# sdr_3157.net
KiCad netlist of a schematic drawn in EAGLE
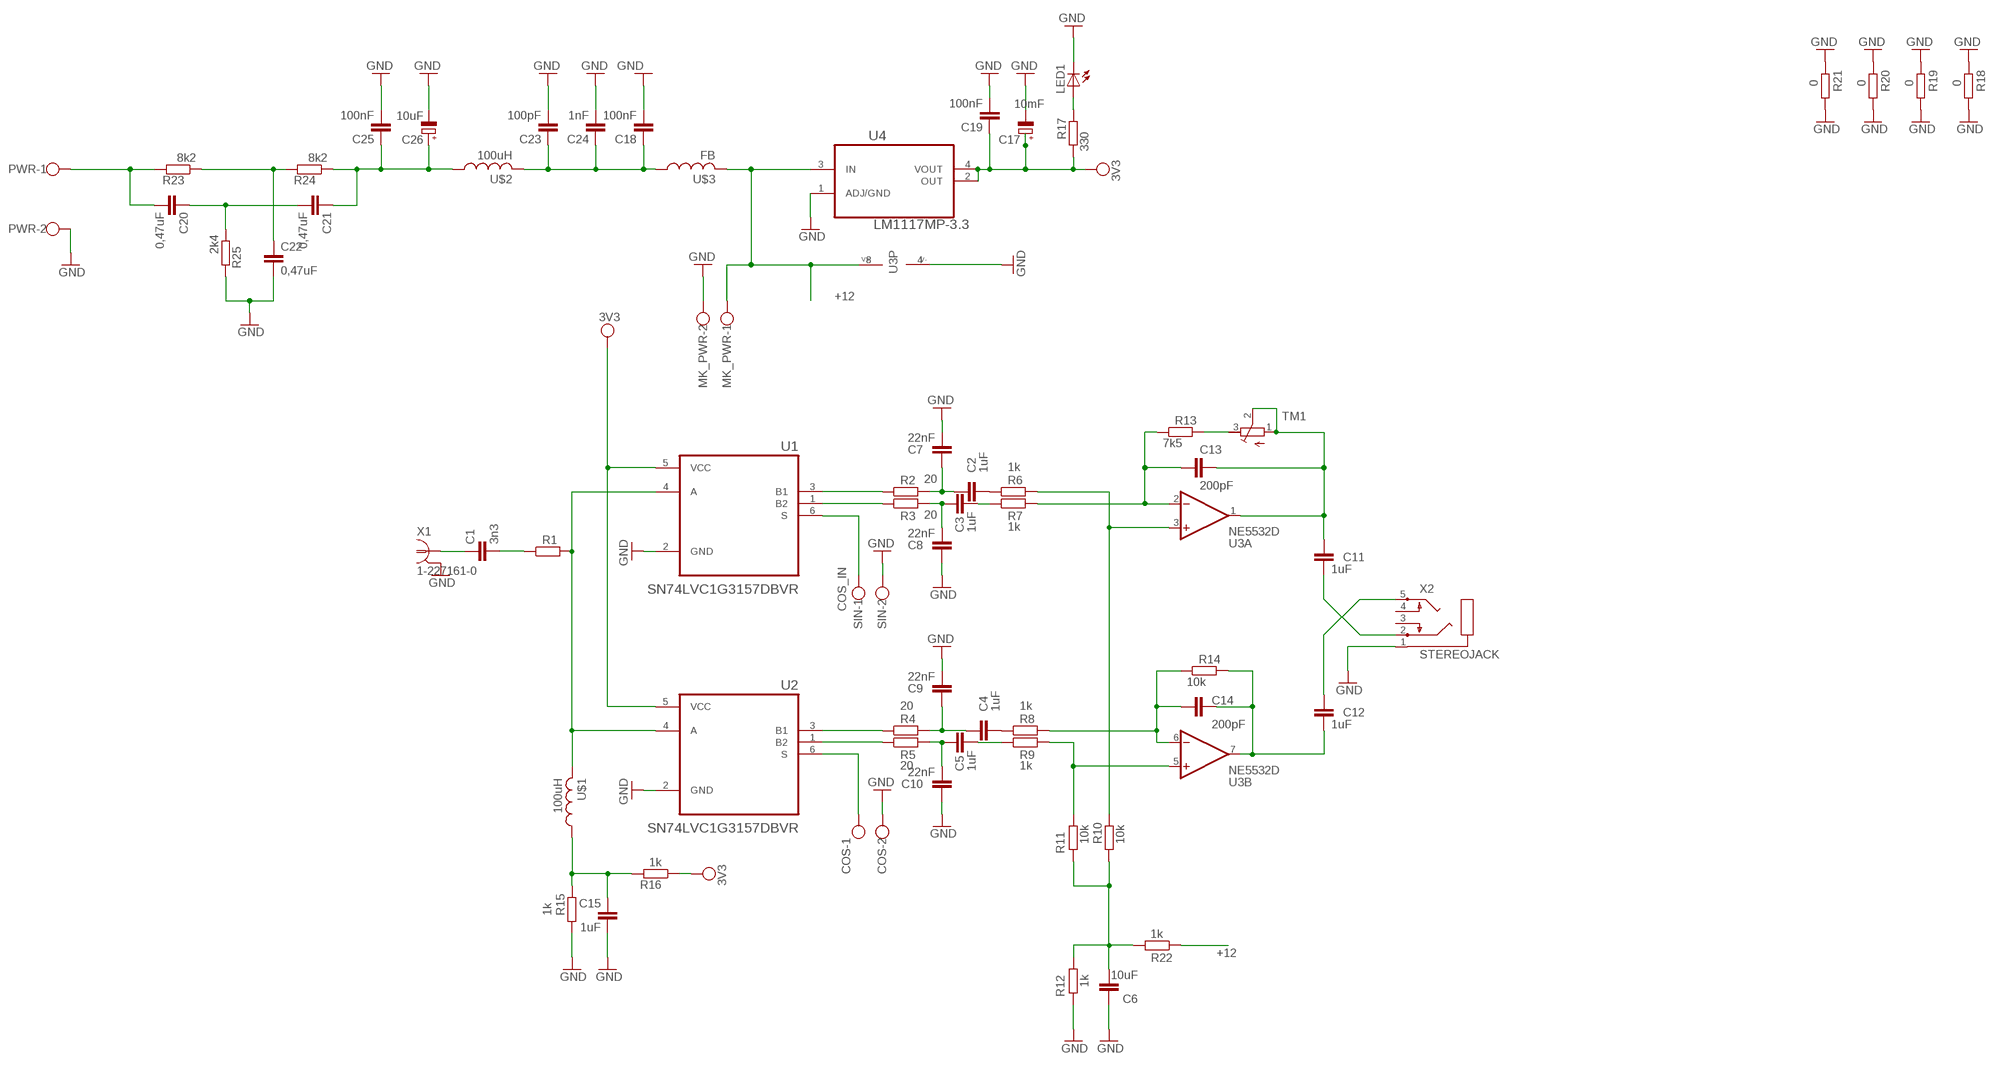
[diagram p0: schematic, sheet 1]

(export (version "E")
  (design (tool "Eeschema 10.0.6"))
  (components
    (comp (ref "C1")
      (value "3n3")
      (footprint "eagle-import:C0805")
      (libsource (lib "eagle-import") (part "C-EUC0805"))
    )
    (comp (ref "C2")
      (value "1uF")
      (footprint "eagle-import:C0805")
      (libsource (lib "eagle-import") (part "C-EUC0805"))
    )
    (comp (ref "C3")
      (value "1uF")
      (footprint "eagle-import:C0805")
      (libsource (lib "eagle-import") (part "C-EUC0805"))
    )
    (comp (ref "C4")
      (value "1uF")
      (footprint "eagle-import:C0805")
      (libsource (lib "eagle-import") (part "C-EUC0805"))
    )
    (comp (ref "C5")
      (value "1uF")
      (footprint "eagle-import:C0805")
      (libsource (lib "eagle-import") (part "C-EUC0805"))
    )
    (comp (ref "C6")
      (value "10uF")
      (footprint "eagle-import:C0805")
      (libsource (lib "eagle-import") (part "C-EUC0805"))
    )
    (comp (ref "C7")
      (value "22nF")
      (footprint "eagle-import:C0805")
      (libsource (lib "eagle-import") (part "C-EUC0805"))
    )
    (comp (ref "C8")
      (value "22nF")
      (footprint "eagle-import:C0805")
      (libsource (lib "eagle-import") (part "C-EUC0805"))
    )
    (comp (ref "C9")
      (value "22nF")
      (footprint "eagle-import:C0805")
      (libsource (lib "eagle-import") (part "C-EUC0805"))
    )
    (comp (ref "C10")
      (value "22nF")
      (footprint "eagle-import:C0805")
      (libsource (lib "eagle-import") (part "C-EUC0805"))
    )
    (comp (ref "C11")
      (value "1uF")
      (footprint "eagle-import:C1210K")
      (libsource (lib "eagle-import") (part "C-EUC1210K"))
    )
    (comp (ref "C12")
      (value "1uF")
      (footprint "eagle-import:C1210K")
      (libsource (lib "eagle-import") (part "C-EUC1210K"))
    )
    (comp (ref "C13")
      (value "200pF")
      (footprint "eagle-import:C0805")
      (libsource (lib "eagle-import") (part "C-EUC0805"))
    )
    (comp (ref "C14")
      (value "200pF")
      (footprint "eagle-import:C0805")
      (libsource (lib "eagle-import") (part "C-EUC0805"))
    )
    (comp (ref "C15")
      (value "1uF")
      (footprint "eagle-import:C0805")
      (libsource (lib "eagle-import") (part "C-EUC0805"))
    )
    (comp (ref "C17")
      (value "10mF")
      (footprint "eagle-import:SMC_C")
      (libsource (lib "eagle-import") (part "CPOL-EUSMCC"))
    )
    (comp (ref "C18")
      (value "100nF")
      (footprint "eagle-import:C0805")
      (libsource (lib "eagle-import") (part "C-EUC0805"))
    )
    (comp (ref "C19")
      (value "100nF")
      (footprint "eagle-import:C0805")
      (libsource (lib "eagle-import") (part "C-EUC0805"))
    )
    (comp (ref "C20")
      (value "0,47uF")
      (footprint "eagle-import:C0805")
      (libsource (lib "eagle-import") (part "C-EUC0805"))
    )
    (comp (ref "C21")
      (value "0,47uF")
      (footprint "eagle-import:C0805")
      (libsource (lib "eagle-import") (part "C-EUC0805"))
    )
    (comp (ref "C22")
      (value "0,47uF")
      (footprint "eagle-import:C0805")
      (libsource (lib "eagle-import") (part "C-EUC0805"))
    )
    (comp (ref "C23")
      (value "100pF")
      (footprint "eagle-import:C0805")
      (libsource (lib "eagle-import") (part "C-EUC0805"))
    )
    (comp (ref "C24")
      (value "1nF")
      (footprint "eagle-import:C0805")
      (libsource (lib "eagle-import") (part "C-EUC0805"))
    )
    (comp (ref "C25")
      (value "100nF")
      (footprint "eagle-import:C0805")
      (libsource (lib "eagle-import") (part "C-EUC0805"))
    )
    (comp (ref "C26")
      (value "10uF")
      (footprint "eagle-import:SMC_C")
      (libsource (lib "eagle-import") (part "CPOL-EUSMCC"))
    )
    (comp (ref "COS")
      (value "W237-102")
      (footprint "eagle-import:W237-102")
      (fields (field (name "MPN") "237-102"))
      (libsource (lib "eagle-import") (part "W237-102"))
    )
    (comp (ref "LED1")
      (value "LEDSMT1206")
      (footprint "eagle-import:1206")
      (libsource (lib "eagle-import") (part "LEDSMT1206"))
    )
    (comp (ref "MK_PWR")
      (value "W237-102")
      (footprint "eagle-import:W237-102")
      (fields (field (name "MPN") "237-102"))
      (libsource (lib "eagle-import") (part "W237-102"))
    )
    (comp (ref "PWR")
      (value "W237-102")
      (footprint "eagle-import:W237-102")
      (fields (field (name "MPN") "237-102"))
      (libsource (lib "eagle-import") (part "W237-102"))
    )
    (comp (ref "R1")
      (value "R-EU_R0805")
      (footprint "eagle-import:R0805")
      (libsource (lib "eagle-import") (part "R-EU_R0805"))
    )
    (comp (ref "R2")
      (value "20")
      (footprint "eagle-import:R0805")
      (libsource (lib "eagle-import") (part "R-EU_R0805"))
    )
    (comp (ref "R3")
      (value "20")
      (footprint "eagle-import:R0805")
      (libsource (lib "eagle-import") (part "R-EU_R0805"))
    )
    (comp (ref "R4")
      (value "20")
      (footprint "eagle-import:R0805")
      (libsource (lib "eagle-import") (part "R-EU_R0805"))
    )
    (comp (ref "R5")
      (value "20")
      (footprint "eagle-import:R0805")
      (libsource (lib "eagle-import") (part "R-EU_R0805"))
    )
    (comp (ref "R6")
      (value "1k")
      (footprint "eagle-import:R0805")
      (libsource (lib "eagle-import") (part "R-EU_R0805"))
    )
    (comp (ref "R7")
      (value "1k")
      (footprint "eagle-import:R0805")
      (libsource (lib "eagle-import") (part "R-EU_R0805"))
    )
    (comp (ref "R8")
      (value "1k")
      (footprint "eagle-import:0204_7")
      (libsource (lib "eagle-import") (part "R-EU_0204/7"))
    )
    (comp (ref "R9")
      (value "1k")
      (footprint "eagle-import:R0805")
      (libsource (lib "eagle-import") (part "R-EU_R0805"))
    )
    (comp (ref "R10")
      (value "10k")
      (footprint "eagle-import:R0805")
      (libsource (lib "eagle-import") (part "R-EU_R0805"))
    )
    (comp (ref "R11")
      (value "10k")
      (footprint "eagle-import:0207_12")
      (libsource (lib "eagle-import") (part "R-EU_0207/12"))
    )
    (comp (ref "R12")
      (value "1k")
      (footprint "eagle-import:M0805")
      (libsource (lib "eagle-import") (part "R-EU_M0805"))
    )
    (comp (ref "R13")
      (value "7k5")
      (footprint "eagle-import:R0805")
      (libsource (lib "eagle-import") (part "R-EU_R0805"))
    )
    (comp (ref "R14")
      (value "10k")
      (footprint "eagle-import:R0805")
      (libsource (lib "eagle-import") (part "R-EU_R0805"))
    )
    (comp (ref "R15")
      (value "1k")
      (footprint "eagle-import:R0805")
      (libsource (lib "eagle-import") (part "R-EU_R0805"))
    )
    (comp (ref "R16")
      (value "1k")
      (footprint "eagle-import:R0805")
      (libsource (lib "eagle-import") (part "R-EU_R0805"))
    )
    (comp (ref "R17")
      (value "330")
      (footprint "eagle-import:R0805")
      (libsource (lib "eagle-import") (part "R-EU_R0805"))
    )
    (comp (ref "R18")
      (value "0")
      (footprint "eagle-import:0207_12")
      (libsource (lib "eagle-import") (part "R-EU_0207/12"))
    )
    (comp (ref "R19")
      (value "0")
      (footprint "eagle-import:0207_5V")
      (libsource (lib "eagle-import") (part "R-EU_0207/5V"))
    )
    (comp (ref "R20")
      (value "0")
      (footprint "eagle-import:0204_7")
      (libsource (lib "eagle-import") (part "R-EU_0204/7"))
    )
    (comp (ref "R21")
      (value "0")
      (footprint "eagle-import:0207_12")
      (libsource (lib "eagle-import") (part "R-EU_0207/12"))
    )
    (comp (ref "R22")
      (value "1k")
      (footprint "eagle-import:M0805")
      (libsource (lib "eagle-import") (part "R-EU_M0805"))
    )
    (comp (ref "R23")
      (value "8k2")
      (footprint "eagle-import:R0805")
      (libsource (lib "eagle-import") (part "R-EU_R0805"))
    )
    (comp (ref "R24")
      (value "8k2")
      (footprint "eagle-import:R0805")
      (libsource (lib "eagle-import") (part "R-EU_R0805"))
    )
    (comp (ref "R25")
      (value "2k4")
      (footprint "eagle-import:R0805")
      (libsource (lib "eagle-import") (part "R-EU_R0805"))
    )
    (comp (ref "SIN")
      (value "W237-102")
      (footprint "eagle-import:W237-102")
      (fields (field (name "MPN") "237-102"))
      (libsource (lib "eagle-import") (part "W237-102"))
    )
    (comp (ref "TM1")
      (value "5k")
      (footprint "eagle-import:RTRIM3296W")
      (libsource (lib "eagle-import") (part "R-TRIMM3296W"))
    )
    (comp (ref "U$1")
      (value "100uH")
      (footprint "eagle-import:LQH55")
      (libsource (lib "eagle-import") (part "L-LQH55"))
    )
    (comp (ref "U$2")
      (value "100uH")
      (footprint "eagle-import:LQH55")
      (libsource (lib "eagle-import") (part "L-LQH55"))
    )
    (comp (ref "U$3") (value "FB") (footprint "eagle-import:FB") (libsource (lib "eagle-import") (part "FB")))
    (comp (ref "U1")
      (value "SN74LVC1G3157DBVR")
      (footprint "eagle-import:SOT95P280X145-6N")
      (fields (field (name "MF") "Texas Instruments"))
      (libsource (lib "eagle-import") (part "SN74LVC1G3157DBVR"))
    )
    (comp (ref "U2")
      (value "SN74LVC1G3157DBVR")
      (footprint "eagle-import:SOT95P280X145-6N")
      (fields (field (name "MF") "Texas Instruments"))
      (libsource (lib "eagle-import") (part "SN74LVC1G3157DBVR"))
    )
    (comp (ref "U3")
      (value "NE5532D")
      (footprint "eagle-import:SO08")
      (libsource (lib "eagle-import") (part "NE5532D"))
    )
    (comp (ref "U4")
      (value "LM1117MP-3.3")
      (footprint "eagle-import:SOT230P696X180-4N")
      (fields (field (name "MF") "Texas Instruments"))
      (libsource (lib "eagle-import") (part "LM1117MP-3.3"))
    )
    (comp (ref "X1")
      (value "1-227161-0")
      (footprint "eagle-import:AMP_227161")
      (fields (field (name "MF") "TYCO ELECTRONICS") (field (name "MPN") "1-227161"))
      (libsource (lib "eagle-import") (part "?2271611--0"))
    )
    (comp (ref "X2")
      (value "STEREOJACK")
      (footprint "eagle-import:STX3100")
      (libsource (lib "eagle-import") (part "STEREOJACK"))
    )
  )
  (nets
    (net (code "1") (name "/+12") (class "Default")
      (node (ref "MK_PWR") (pin "1") (pinfunction "KL_1") (pintype "passive"))
      (node (ref "R22") (pin "1") (pinfunction "1_1") (pintype "passive"))
      (node (ref "U$3") (pin "P$2") (pinfunction "2_P$2") (pintype "passive"))
      (node (ref "U3") (pin "8") (pinfunction "V+_8") (pintype "power_in"))
      (node (ref "U4") (pin "3") (pinfunction "IN_3") (pintype "input"))
    )
    (net (code "2") (name "/COS_IN") (class "Default")
      (node (ref "SIN") (pin "1") (pinfunction "KL_1") (pintype "passive"))
      (node (ref "U1") (pin "6") (pinfunction "S_6") (pintype "input"))
    )
    (net (code "3") (name "3V3") (class "Default")
      (node (ref "C17") (pin "+") (pinfunction "+_+") (pintype "passive"))
      (node (ref "C19") (pin "1") (pinfunction "1_1") (pintype "passive"))
      (node (ref "R16") (pin "1") (pinfunction "1_1") (pintype "passive"))
      (node (ref "R17") (pin "1") (pinfunction "1_1") (pintype "passive"))
      (node (ref "U1") (pin "5") (pinfunction "VCC_5") (pintype "power_in"))
      (node (ref "U2") (pin "5") (pinfunction "VCC_5") (pintype "power_in"))
      (node (ref "U4") (pin "2") (pinfunction "OUT_2") (pintype "output"))
      (node (ref "U4") (pin "4") (pinfunction "VOUT_4") (pintype "output"))
    )
    (net (code "4") (name "GND") (class "Default")
      (node (ref "C10") (pin "1") (pinfunction "1_1") (pintype "passive"))
      (node (ref "C15") (pin "1") (pinfunction "1_1") (pintype "passive"))
      (node (ref "C17") (pin "-") (pinfunction "-_-") (pintype "passive"))
      (node (ref "C18") (pin "2") (pinfunction "2_2") (pintype "passive"))
      (node (ref "C19") (pin "2") (pinfunction "2_2") (pintype "passive"))
      (node (ref "C22") (pin "2") (pinfunction "2_2") (pintype "passive"))
      (node (ref "C23") (pin "2") (pinfunction "2_2") (pintype "passive"))
      (node (ref "C24") (pin "2") (pinfunction "2_2") (pintype "passive"))
      (node (ref "C25") (pin "2") (pinfunction "2_2") (pintype "passive"))
      (node (ref "C26") (pin "-") (pinfunction "-_-") (pintype "passive"))
      (node (ref "C6") (pin "1") (pinfunction "1_1") (pintype "passive"))
      (node (ref "C7") (pin "2") (pinfunction "2_2") (pintype "passive"))
      (node (ref "C8") (pin "1") (pinfunction "1_1") (pintype "passive"))
      (node (ref "C9") (pin "2") (pinfunction "2_2") (pintype "passive"))
      (node (ref "COS") (pin "2") (pinfunction "KL_2") (pintype "passive"))
      (node (ref "LED1") (pin "C") (pinfunction "C_C") (pintype "passive"))
      (node (ref "MK_PWR") (pin "2") (pinfunction "KL_2") (pintype "passive"))
      (node (ref "PWR") (pin "2") (pinfunction "KL_2") (pintype "passive"))
      (node (ref "R12") (pin "1") (pinfunction "1_1") (pintype "passive"))
      (node (ref "R15") (pin "1") (pinfunction "1_1") (pintype "passive"))
      (node (ref "R18") (pin "1") (pinfunction "1_1") (pintype "passive"))
      (node (ref "R18") (pin "2") (pinfunction "2_2") (pintype "passive"))
      (node (ref "R19") (pin "1") (pinfunction "1_1") (pintype "passive"))
      (node (ref "R19") (pin "2") (pinfunction "2_2") (pintype "passive"))
      (node (ref "R20") (pin "1") (pinfunction "1_1") (pintype "passive"))
      (node (ref "R20") (pin "2") (pinfunction "2_2") (pintype "passive"))
      (node (ref "R21") (pin "1") (pinfunction "1_1") (pintype "passive"))
      (node (ref "R21") (pin "2") (pinfunction "2_2") (pintype "passive"))
      (node (ref "R25") (pin "2") (pinfunction "2_2") (pintype "passive"))
      (node (ref "SIN") (pin "2") (pinfunction "KL_2") (pintype "passive"))
      (node (ref "U1") (pin "2") (pinfunction "GND_2") (pintype "power_in"))
      (node (ref "U2") (pin "2") (pinfunction "GND_2") (pintype "power_in"))
      (node (ref "U3") (pin "4") (pinfunction "V-_4") (pintype "power_in"))
      (node (ref "U4") (pin "1") (pinfunction "ADJ/GND_1") (pintype "passive"))
      (node (ref "X1") (pin "2") (pinfunction "2_2") (pintype "passive"))
      (node (ref "X2") (pin "1") (pinfunction "1_1") (pintype "passive"))
    )
    (net (code "5") (name "Net-(C1-Pad1)") (class "Default")
      (node (ref "C1") (pin "1") (pinfunction "1_1") (pintype "passive"))
      (node (ref "X1") (pin "1") (pinfunction "1_1") (pintype "passive"))
    )
    (net (code "6") (name "Net-(C1-Pad2)") (class "Default")
      (node (ref "C1") (pin "2") (pinfunction "2_2") (pintype "passive"))
      (node (ref "R1") (pin "1") (pinfunction "1_1") (pintype "passive"))
    )
    (net (code "7") (name "Net-(C2-Pad1)") (class "Default")
      (node (ref "C2") (pin "1") (pinfunction "1_1") (pintype "passive"))
      (node (ref "C7") (pin "1") (pinfunction "1_1") (pintype "passive"))
      (node (ref "R2") (pin "2") (pinfunction "2_2") (pintype "passive"))
    )
    (net (code "8") (name "Net-(C2-Pad2)") (class "Default")
      (node (ref "C2") (pin "2") (pinfunction "2_2") (pintype "passive"))
      (node (ref "R6") (pin "1") (pinfunction "1_1") (pintype "passive"))
    )
    (net (code "9") (name "Net-(C3-Pad1)") (class "Default")
      (node (ref "C3") (pin "1") (pinfunction "1_1") (pintype "passive"))
      (node (ref "C8") (pin "2") (pinfunction "2_2") (pintype "passive"))
      (node (ref "R3") (pin "2") (pinfunction "2_2") (pintype "passive"))
    )
    (net (code "10") (name "Net-(C3-Pad2)") (class "Default")
      (node (ref "C3") (pin "2") (pinfunction "2_2") (pintype "passive"))
      (node (ref "R7") (pin "1") (pinfunction "1_1") (pintype "passive"))
    )
    (net (code "11") (name "Net-(C4-Pad1)") (class "Default")
      (node (ref "C4") (pin "1") (pinfunction "1_1") (pintype "passive"))
      (node (ref "C9") (pin "1") (pinfunction "1_1") (pintype "passive"))
      (node (ref "R4") (pin "2") (pinfunction "2_2") (pintype "passive"))
    )
    (net (code "12") (name "Net-(C4-Pad2)") (class "Default")
      (node (ref "C4") (pin "2") (pinfunction "2_2") (pintype "passive"))
      (node (ref "R8") (pin "1") (pinfunction "1_1") (pintype "passive"))
    )
    (net (code "13") (name "Net-(C5-Pad2)") (class "Default")
      (node (ref "C5") (pin "2") (pinfunction "2_2") (pintype "passive"))
      (node (ref "R9") (pin "1") (pinfunction "1_1") (pintype "passive"))
    )
    (net (code "14") (name "Net-(C6-Pad2)") (class "Default")
      (node (ref "C6") (pin "2") (pinfunction "2_2") (pintype "passive"))
      (node (ref "R10") (pin "1") (pinfunction "1_1") (pintype "passive"))
      (node (ref "R11") (pin "1") (pinfunction "1_1") (pintype "passive"))
      (node (ref "R12") (pin "2") (pinfunction "2_2") (pintype "passive"))
      (node (ref "R22") (pin "2") (pinfunction "2_2") (pintype "passive"))
    )
    (net (code "15") (name "Net-(C10-Pad2)") (class "Default")
      (node (ref "C10") (pin "2") (pinfunction "2_2") (pintype "passive"))
      (node (ref "C5") (pin "1") (pinfunction "1_1") (pintype "passive"))
      (node (ref "R5") (pin "2") (pinfunction "2_2") (pintype "passive"))
    )
    (net (code "16") (name "Net-(C11-Pad2)") (class "Default")
      (node (ref "C11") (pin "2") (pinfunction "2_2") (pintype "passive"))
      (node (ref "X2") (pin "2") (pinfunction "2_2") (pintype "passive"))
    )
    (net (code "17") (name "Net-(C12-Pad1)") (class "Default")
      (node (ref "C12") (pin "1") (pinfunction "1_1") (pintype "passive"))
      (node (ref "X2") (pin "5") (pinfunction "5_5") (pintype "passive"))
    )
    (net (code "18") (name "Net-(C15-Pad2)") (class "Default")
      (node (ref "C15") (pin "2") (pinfunction "2_2") (pintype "passive"))
      (node (ref "R15") (pin "2") (pinfunction "2_2") (pintype "passive"))
      (node (ref "R16") (pin "2") (pinfunction "2_2") (pintype "passive"))
      (node (ref "U$1") (pin "1") (pinfunction "1_1") (pintype "passive"))
    )
    (net (code "19") (name "Net-(C20-Pad1)") (class "Default")
      (node (ref "C20") (pin "1") (pinfunction "1_1") (pintype "passive"))
      (node (ref "C21") (pin "2") (pinfunction "2_2") (pintype "passive"))
      (node (ref "R25") (pin "1") (pinfunction "1_1") (pintype "passive"))
    )
    (net (code "20") (name "Net-(C21-Pad1)") (class "Default")
      (node (ref "C21") (pin "1") (pinfunction "1_1") (pintype "passive"))
      (node (ref "C25") (pin "1") (pinfunction "1_1") (pintype "passive"))
      (node (ref "C26") (pin "+") (pinfunction "+_+") (pintype "passive"))
      (node (ref "R24") (pin "1") (pinfunction "1_1") (pintype "passive"))
      (node (ref "U$2") (pin "1") (pinfunction "1_1") (pintype "passive"))
    )
    (net (code "21") (name "Net-(C22-Pad1)") (class "Default")
      (node (ref "C22") (pin "1") (pinfunction "1_1") (pintype "passive"))
      (node (ref "R23") (pin "1") (pinfunction "1_1") (pintype "passive"))
      (node (ref "R24") (pin "2") (pinfunction "2_2") (pintype "passive"))
    )
    (net (code "22") (name "Net-(COSA-KL)") (class "Default")
      (node (ref "COS") (pin "1") (pinfunction "KL_1") (pintype "passive"))
      (node (ref "U2") (pin "6") (pinfunction "S_6") (pintype "input"))
    )
    (net (code "23") (name "Net-(LED1-PadA)") (class "Default")
      (node (ref "LED1") (pin "A") (pinfunction "A_A") (pintype "passive"))
      (node (ref "R17") (pin "2") (pinfunction "2_2") (pintype "passive"))
    )
    (net (code "24") (name "Net-(PWRA-KL)") (class "Default")
      (node (ref "C20") (pin "2") (pinfunction "2_2") (pintype "passive"))
      (node (ref "PWR") (pin "1") (pinfunction "KL_1") (pintype "passive"))
      (node (ref "R23") (pin "2") (pinfunction "2_2") (pintype "passive"))
    )
    (net (code "25") (name "Net-(TM1-A)") (class "Default")
      (node (ref "C11") (pin "1") (pinfunction "1_1") (pintype "passive"))
      (node (ref "C13") (pin "2") (pinfunction "2_2") (pintype "passive"))
      (node (ref "TM1") (pin "1") (pinfunction "A_1") (pintype "passive"))
      (node (ref "TM1") (pin "2") (pinfunction "S_2") (pintype "passive"))
      (node (ref "U3") (pin "1") (pinfunction "OUT_1") (pintype "output"))
    )
    (net (code "26") (name "Net-(TM1-E)") (class "Default")
      (node (ref "R13") (pin "2") (pinfunction "2_2") (pintype "passive"))
      (node (ref "TM1") (pin "3") (pinfunction "E_3") (pintype "passive"))
    )
    (net (code "27") (name "Net-(U$3-1)") (class "Default")
      (node (ref "C18") (pin "1") (pinfunction "1_1") (pintype "passive"))
      (node (ref "C23") (pin "1") (pinfunction "1_1") (pintype "passive"))
      (node (ref "C24") (pin "1") (pinfunction "1_1") (pintype "passive"))
      (node (ref "U$2") (pin "2") (pinfunction "2_2") (pintype "passive"))
      (node (ref "U$3") (pin "P$1") (pinfunction "1_P$1") (pintype "passive"))
    )
    (net (code "28") (name "Net-(U1-A)") (class "Default")
      (node (ref "R1") (pin "2") (pinfunction "2_2") (pintype "passive"))
      (node (ref "U$1") (pin "2") (pinfunction "2_2") (pintype "passive"))
      (node (ref "U1") (pin "4") (pinfunction "A_4") (pintype "output"))
      (node (ref "U2") (pin "4") (pinfunction "A_4") (pintype "output"))
    )
    (net (code "29") (name "Net-(U1-B1)") (class "Default")
      (node (ref "R2") (pin "1") (pinfunction "1_1") (pintype "passive"))
      (node (ref "U1") (pin "3") (pinfunction "B1_3") (pintype "input"))
    )
    (net (code "30") (name "Net-(U1-B2)") (class "Default")
      (node (ref "R3") (pin "1") (pinfunction "1_1") (pintype "passive"))
      (node (ref "U1") (pin "1") (pinfunction "B2_1") (pintype "input"))
    )
    (net (code "31") (name "Net-(U2-B1)") (class "Default")
      (node (ref "R4") (pin "1") (pinfunction "1_1") (pintype "passive"))
      (node (ref "U2") (pin "3") (pinfunction "B1_3") (pintype "input"))
    )
    (net (code "32") (name "Net-(U2-B2)") (class "Default")
      (node (ref "R5") (pin "1") (pinfunction "1_1") (pintype "passive"))
      (node (ref "U2") (pin "1") (pinfunction "B2_1") (pintype "input"))
    )
    (net (code "33") (name "Net-(U3A-+IN)") (class "Default")
      (node (ref "R10") (pin "2") (pinfunction "2_2") (pintype "passive"))
      (node (ref "R6") (pin "2") (pinfunction "2_2") (pintype "passive"))
      (node (ref "U3") (pin "3") (pinfunction "+IN_3") (pintype "input"))
    )
    (net (code "34") (name "Net-(U3A--IN)") (class "Default")
      (node (ref "C13") (pin "1") (pinfunction "1_1") (pintype "passive"))
      (node (ref "R13") (pin "1") (pinfunction "1_1") (pintype "passive"))
      (node (ref "R7") (pin "2") (pinfunction "2_2") (pintype "passive"))
      (node (ref "U3") (pin "2") (pinfunction "-IN_2") (pintype "input"))
    )
    (net (code "35") (name "Net-(U3B-+IN)") (class "Default")
      (node (ref "R11") (pin "2") (pinfunction "2_2") (pintype "passive"))
      (node (ref "R9") (pin "2") (pinfunction "2_2") (pintype "passive"))
      (node (ref "U3") (pin "5") (pinfunction "+IN_5") (pintype "input"))
    )
    (net (code "36") (name "Net-(U3B--IN)") (class "Default")
      (node (ref "C14") (pin "1") (pinfunction "1_1") (pintype "passive"))
      (node (ref "R14") (pin "1") (pinfunction "1_1") (pintype "passive"))
      (node (ref "R8") (pin "2") (pinfunction "2_2") (pintype "passive"))
      (node (ref "U3") (pin "6") (pinfunction "-IN_6") (pintype "input"))
    )
    (net (code "37") (name "Net-(U3B-OUT)") (class "Default")
      (node (ref "C12") (pin "2") (pinfunction "2_2") (pintype "passive"))
      (node (ref "C14") (pin "2") (pinfunction "2_2") (pintype "passive"))
      (node (ref "R14") (pin "2") (pinfunction "2_2") (pintype "passive"))
      (node (ref "U3") (pin "7") (pinfunction "OUT_7") (pintype "output"))
    )
    (net (code "38") (name "unconnected-(X2-Pad3)") (class "Default")
      (node (ref "X2") (pin "3") (pinfunction "3_3") (pintype "passive"))
    )
    (net (code "39") (name "unconnected-(X2-Pad4)") (class "Default")
      (node (ref "X2") (pin "4") (pinfunction "4_4") (pintype "passive"))
    )
  )
)
